# 3_3-5_and_5-3_3_Level_Shifters.net
KiCad netlist of a schematic drawn in Altium Designer
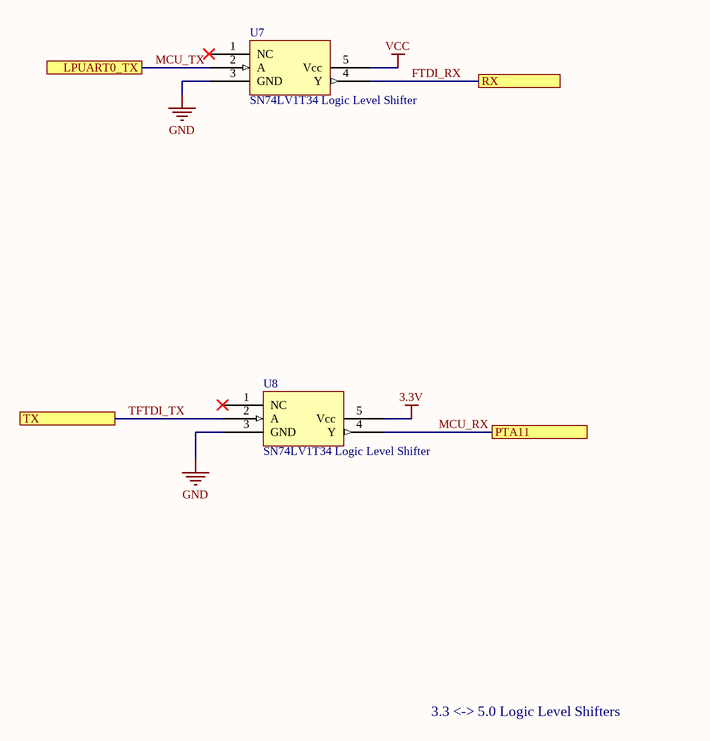
[diagram p0: 3.3-5 and 5-3.3 Level Shifters.SchDoc]

(export (version "E")
  (design (tool "Eeschema 10.0.6"))
  (components
    (comp (ref "U7")
      (value "SN74LV1T34 Logic Level Shifter")
      (footprint "SOT23-5")
      (description "Logic Level Shifter driven by Vcc")
      (fields (field (name "MFRPARTNO") "SN74LV1T34DBVR"))
      (libsource (lib "Altium-Lib") (part "SN74LV1T34 Logic Level Shifter"))
    )
    (comp (ref "U8")
      (value "SN74LV1T34 Logic Level Shifter")
      (footprint "SOT23-5")
      (description "Logic Level Shifter driven by Vcc")
      (fields (field (name "MFRPARTNO") "SN74LV1T34DBVR"))
      (libsource (lib "Altium-Lib") (part "SN74LV1T34 Logic Level Shifter"))
    )
  )
  (nets
    (net (code "1") (name "/FTDI_RX") (class "Default")
      (node (ref "U7") (pin "4") (pinfunction "Y_4") (pintype "output"))
    )
    (net (code "2") (name "/MCU_RX") (class "Default")
      (node (ref "U8") (pin "4") (pinfunction "Y_4") (pintype "output"))
    )
    (net (code "3") (name "/MCU_TX") (class "Default")
      (node (ref "U7") (pin "2") (pinfunction "A_2") (pintype "input"))
    )
    (net (code "4") (name "/TFTDI_TX") (class "Default")
      (node (ref "U8") (pin "2") (pinfunction "A_2") (pintype "input"))
    )
    (net (code "5") (name "3.3V") (class "Default")
      (node (ref "U8") (pin "5") (pinfunction "Vcc_5") (pintype "power_in"))
    )
    (net (code "6") (name "GND") (class "Default")
      (node (ref "U7") (pin "3") (pinfunction "GND_3") (pintype "power_in"))
      (node (ref "U8") (pin "3") (pinfunction "GND_3") (pintype "power_in"))
    )
    (net (code "7") (name "VCC") (class "Default")
      (node (ref "U7") (pin "5") (pinfunction "Vcc_5") (pintype "power_in"))
    )
    (net (code "8") (name "unconnected-(U7-NC-Pad1)") (class "Default")
      (node (ref "U7") (pin "1") (pinfunction "NC_1") (pintype "passive+no_connect"))
    )
    (net (code "9") (name "unconnected-(U8-NC-Pad1)") (class "Default")
      (node (ref "U8") (pin "1") (pinfunction "NC_1") (pintype "passive+no_connect"))
    )
  )
)
